# POWER.net
KiCad netlist of a schematic drawn in Altium Designer
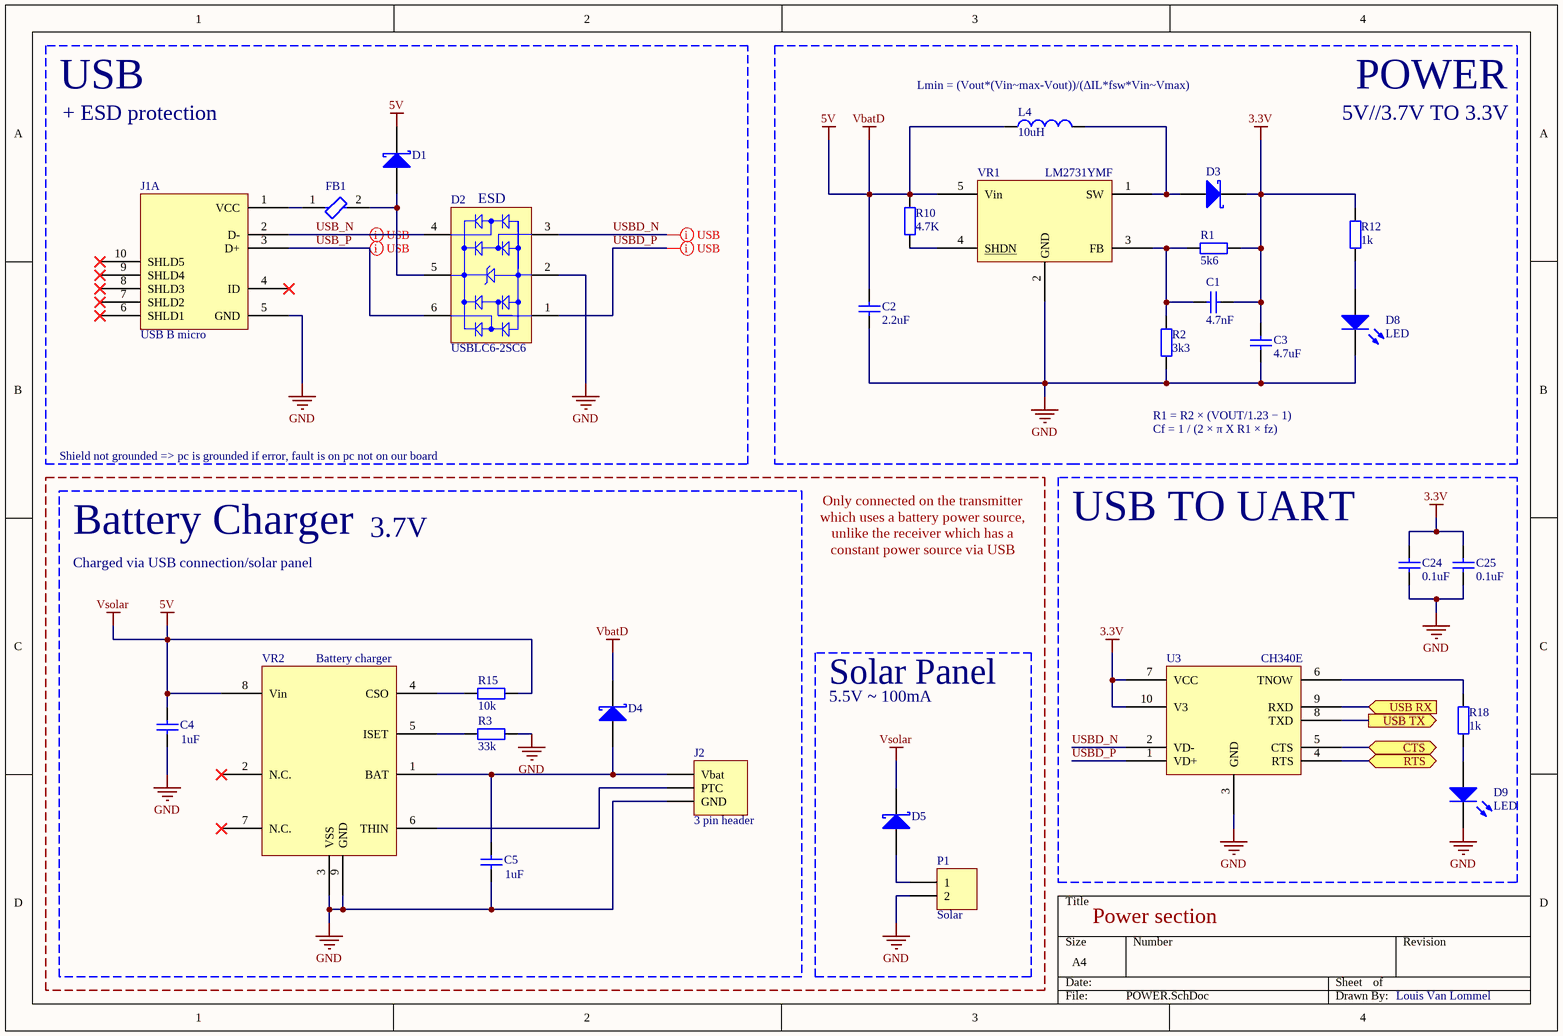
[diagram p0: POWER.SchDoc]

(export (version "E")
  (design (tool "Eeschema 10.0.6"))
  (components
    (comp (ref "C1")
      (value "Cf = 1 / (2 × π X R1 × fz)")
      (footprint "CAP_0603")
      (description "Capacitor")
      (fields (field (name "ALTIUM_VALUE") "4.7nF") (field (name "PUBLISHER") "Altium Limited"))
      (libsource (lib "Miscellaneous Devices") (part "Cap"))
    )
    (comp (ref "C2")
      (value "2.2uF")
      (footprint "CAP_1210")
      (description "Capacitor")
      (fields (field (name "PUBLISHER") "Altium Limited"))
      (libsource (lib "Miscellaneous Devices") (part "Cap"))
    )
    (comp (ref "C3")
      (value "4.7uF")
      (footprint "CAP_1210")
      (description "Capacitor")
      (fields (field (name "PUBLISHER") "Altium Limited"))
      (libsource (lib "Miscellaneous Devices") (part "Cap"))
    )
    (comp (ref "C4")
      (value "1uF")
      (footprint "CAP_0603")
      (description "Capacitor")
      (fields (field (name "PUBLISHER") "Altium Limited"))
      (libsource (lib "Miscellaneous Devices") (part "Cap"))
    )
    (comp (ref "C5")
      (value "1uF")
      (footprint "CAP_0603")
      (description "Capacitor")
      (fields (field (name "PUBLISHER") "Altium Limited"))
      (libsource (lib "Miscellaneous Devices") (part "Cap"))
    )
    (comp (ref "C24")
      (value "0.1uF")
      (footprint "CAP_0603")
      (description "Capacitor")
      (fields (field (name "PUBLISHER") "Altium Limited"))
      (libsource (lib "Miscellaneous Devices") (part "Cap"))
    )
    (comp (ref "C25")
      (value "0.1uF")
      (footprint "CAP_0603")
      (description "Capacitor")
      (fields (field (name "PUBLISHER") "Altium Limited"))
      (libsource (lib "Miscellaneous Devices") (part "Cap"))
    )
    (comp (ref "D1")
      (value "~")
      (footprint "SOT-23_L")
      (description "Silicon RF Schottky Diode for Mixer Applications in the VHF/UHF Range")
      (fields (field (name "PUBLISHER") "Altium Limited"))
      (libsource (lib "Miscellaneous Devices") (part "Diode BAT17"))
    )
    (comp (ref "D2")
      (value "USBLC6-2SC6")
      (footprint "STM-SOT23-6L_V")
      (description "Very low capacitance ESD protection, 3.5 pF, -40 to 125 degC, 6-Pin SOT23, RoHS, Tape and Reel")
      (fields (field (name "MANUFACTURER") "STMicroelectronics"))
      (libsource (lib "Altium Content Vault") (part "STM-USB_DVI_HDMIULC6-4SC6X-SOT23-6L"))
    )
    (comp (ref "D3")
      (value "~")
      (footprint "SOT-23_L")
      (description "Silicon RF Schottky Diode for Mixer Applications in the VHF/UHF Range")
      (fields (field (name "PUBLISHER") "Altium Limited"))
      (libsource (lib "Miscellaneous Devices") (part "Diode BAT17"))
    )
    (comp (ref "D4")
      (value "~")
      (footprint "SOT-23_L")
      (description "Silicon RF Schottky Diode for Mixer Applications in the VHF/UHF Range")
      (fields (field (name "PUBLISHER") "Altium Limited"))
      (libsource (lib "Miscellaneous Devices") (part "Diode BAT17"))
    )
    (comp (ref "D5")
      (value "~")
      (footprint "SOT-23_L")
      (description "Silicon RF Schottky Diode for Mixer Applications in the VHF/UHF Range")
      (fields (field (name "PUBLISHER") "Altium Limited"))
      (libsource (lib "Miscellaneous Devices") (part "Diode BAT17"))
    )
    (comp (ref "D8")
      (value "LED")
      (footprint "LED_0603")
      (description "Typical RED, GREEN, YELLOW, AMBER GaAs LED")
      (fields (field (name "PUBLISHER") "Altium Limited"))
      (libsource (lib "Miscellaneous Devices") (part "LED2"))
    )
    (comp (ref "D9")
      (value "LED")
      (footprint "LED_0603")
      (description "Typical RED, GREEN, YELLOW, AMBER GaAs LED")
      (fields (field (name "PUBLISHER") "Altium Limited"))
      (libsource (lib "Miscellaneous Devices") (part "LED2"))
    )
    (comp (ref "FB1")
      (value "BLM18PG121SN1D")
      (footprint "FP-BLM18-0_15-t0_8-IPC_A")
      (description "Chip Ferrite Bead, 0603, 120Ω @ 100MHz, 0.05Ω, 25%, 2A")
      (fields (field (name "TOLERANCE") "25%"))
      (libsource (lib "Altium Content Vault") (part "5f30dd21d616792df468990f7003faa"))
    )
    (comp (ref "J1")
      (value "USB B micro")
      (footprint "USB Micro B")
      (libsource (lib "AP2112") (part "USB micro B"))
    )
    (comp (ref "J2")
      (value "3 pin header")
      (footprint "Header_3")
      (libsource (lib "AP2112") (part "Header_3"))
    )
    (comp (ref "L4")
      (value "10uH")
      (footprint "INDP7373X45N")
      (description "Inductor")
      (fields (field (name "PUBLISHER") "Altium Limited"))
      (libsource (lib "Miscellaneous Devices") (part "Inductor"))
    )
    (comp (ref "P1")
      (value "Solar")
      (footprint "HDR1X2")
      (description "Header, 2-Pin, Right Angle")
      (fields (field (name "PUBLISHER") "Altium Limited"))
      (libsource (lib "Miscellaneous Connectors") (part "Header 2H"))
    )
    (comp (ref "R1")
      (value "R1 = R2 × (VOUT/1.23 − 1)")
      (footprint "RES_0603")
      (description "Resistor")
      (fields (field (name "ALTIUM_VALUE") "5k6") (field (name "PUBLISHER") "Altium Limited"))
      (libsource (lib "") (part "Res2_2"))
    )
    (comp (ref "R2")
      (value "3k3")
      (footprint "RES_0603")
      (description "Resistor")
      (fields (field (name "PUBLISHER") "Altium Limited"))
      (libsource (lib "Miscellaneous Devices") (part "Res2"))
    )
    (comp (ref "R3")
      (value "33k")
      (footprint "RES_0603")
      (fields (field (name "PUBLISHER") "Altium Limited"))
      (libsource (lib "") (part "Res2_2"))
    )
    (comp (ref "R10")
      (value "4.7K")
      (footprint "RES_0603")
      (description "Resistor")
      (fields (field (name "PUBLISHER") "Altium Limited"))
      (libsource (lib "Miscellaneous Devices") (part "Res2"))
    )
    (comp (ref "R12")
      (value "1k")
      (footprint "RES_0603")
      (description "Resistor")
      (fields (field (name "PUBLISHER") "Altium Limited"))
      (libsource (lib "") (part "Res2_1"))
    )
    (comp (ref "R15")
      (value "10k")
      (footprint "RES_0603")
      (description "Resistor")
      (fields (field (name "PUBLISHER") "Altium Limited"))
      (libsource (lib "") (part "Res2_2"))
    )
    (comp (ref "R18")
      (value "1k")
      (footprint "RES_0603")
      (description "Resistor")
      (fields (field (name "PUBLISHER") "Altium Limited"))
      (libsource (lib "") (part "Res2_1"))
    )
    (comp (ref "U3")
      (value "CH340E")
      (footprint "MSOP-10")
      (description "USB to Serial Uart")
      (libsource (lib "PE2_Schematics") (part "CH340E"))
    )
    (comp (ref "VR1")
      (value "LM2731YMF")
      (footprint "SOT23-5")
      (description "DC-DC Switching Boost (Step Up) Regulator, Adjustable, 2.7V-14Vin, 1.23V-22Vout, 2Aout, SOT-23-5")
      (libsource (lib "PE2_Schematics") (part "LM2731"))
    )
    (comp (ref "VR2")
      (value "Battery charger")
      (footprint "SOP127P600-8N")
      (libsource (lib "PE2_Schematics") (part "XC6804A3E1QR-G"))
    )
  )
  (nets
    (net (code "1") (name "/CTS") (class "Default")
      (node (ref "U3") (pin "5") (pinfunction "CTS_5") (pintype "passive"))
    )
    (net (code "2") (name "/RTS") (class "Default")
      (node (ref "U3") (pin "4") (pinfunction "RTS_4") (pintype "passive"))
    )
    (net (code "3") (name "/USB RX") (class "Default")
      (node (ref "U3") (pin "9") (pinfunction "RXD_9") (pintype "passive"))
    )
    (net (code "4") (name "/USB TX") (class "Default")
      (node (ref "U3") (pin "8") (pinfunction "TXD_8") (pintype "passive"))
    )
    (net (code "5") (name "/USBD_N") (class "Default")
      (node (ref "D2") (pin "3") (pinfunction "I/O_2_3") (pintype "passive"))
      (node (ref "U3") (pin "2") (pinfunction "VD-_2") (pintype "passive"))
    )
    (net (code "6") (name "/USBD_P") (class "Default")
      (node (ref "D2") (pin "1") (pinfunction "I/O_1_1") (pintype "passive"))
      (node (ref "U3") (pin "1") (pinfunction "VD+_1") (pintype "passive"))
    )
    (net (code "7") (name "/USB_N") (class "Default")
      (node (ref "D2") (pin "4") (pinfunction "I/O_3_4") (pintype "passive"))
      (node (ref "J1") (pin "2") (pinfunction "D-_2") (pintype "passive"))
    )
    (net (code "8") (name "/USB_P") (class "Default")
      (node (ref "D2") (pin "6") (pinfunction "I/O_4_6") (pintype "passive"))
      (node (ref "J1") (pin "3") (pinfunction "D+_3") (pintype "passive"))
    )
    (net (code "9") (name "3.3V") (class "Default")
      (node (ref "C1") (pin "1") (pinfunction "1_1") (pintype "passive"))
      (node (ref "C24") (pin "1") (pinfunction "1_1") (pintype "passive"))
      (node (ref "C25") (pin "1") (pinfunction "1_1") (pintype "passive"))
      (node (ref "C3") (pin "1") (pinfunction "1_1") (pintype "passive"))
      (node (ref "D3") (pin "3") (pinfunction "K_3") (pintype "passive"))
      (node (ref "R1") (pin "1") (pinfunction "1_1") (pintype "passive"))
      (node (ref "R12") (pin "2") (pinfunction "2_2") (pintype "passive"))
      (node (ref "U3") (pin "10") (pinfunction "V3_10") (pintype "passive"))
      (node (ref "U3") (pin "7") (pinfunction "VCC_7") (pintype "passive"))
    )
    (net (code "10") (name "5V") (class "Default")
      (node (ref "C2") (pin "1") (pinfunction "1_1") (pintype "passive"))
      (node (ref "C4") (pin "2") (pinfunction "2_2") (pintype "passive"))
      (node (ref "D1") (pin "3") (pinfunction "K_3") (pintype "passive"))
      (node (ref "D4") (pin "3") (pinfunction "K_3") (pintype "passive"))
      (node (ref "D5") (pin "3") (pinfunction "K_3") (pintype "passive"))
      (node (ref "L4") (pin "1") (pinfunction "1_1") (pintype "passive"))
      (node (ref "R10") (pin "1") (pinfunction "1_1") (pintype "passive"))
      (node (ref "R15") (pin "1") (pinfunction "1_1") (pintype "passive"))
      (node (ref "VR1") (pin "5") (pinfunction "Vin_5") (pintype "passive"))
      (node (ref "VR2") (pin "8") (pinfunction "Vin_8") (pintype "passive"))
    )
    (net (code "11") (name "GND") (class "Default")
      (node (ref "C2") (pin "2") (pinfunction "2_2") (pintype "passive"))
      (node (ref "C24") (pin "2") (pinfunction "2_2") (pintype "passive"))
      (node (ref "C25") (pin "2") (pinfunction "2_2") (pintype "passive"))
      (node (ref "C3") (pin "2") (pinfunction "2_2") (pintype "passive"))
      (node (ref "C4") (pin "1") (pinfunction "1_1") (pintype "passive"))
      (node (ref "C5") (pin "1") (pinfunction "1_1") (pintype "passive"))
      (node (ref "D2") (pin "2") (pinfunction "GND_2") (pintype "passive"))
      (node (ref "D8") (pin "2") (pinfunction "K_2") (pintype "passive"))
      (node (ref "D9") (pin "2") (pinfunction "K_2") (pintype "passive"))
      (node (ref "J1") (pin "5") (pinfunction "GND_5") (pintype "passive"))
      (node (ref "J2") (pin "3") (pinfunction "GND_3") (pintype "passive"))
      (node (ref "P1") (pin "2") (pinfunction "2_2") (pintype "passive"))
      (node (ref "R2") (pin "2") (pinfunction "2_2") (pintype "passive"))
      (node (ref "R3") (pin "1") (pinfunction "1_1") (pintype "passive"))
      (node (ref "U3") (pin "3") (pinfunction "GND_3") (pintype "passive"))
      (node (ref "VR1") (pin "2") (pinfunction "GND_2") (pintype "passive"))
      (node (ref "VR2") (pin "3") (pinfunction "VSS_3") (pintype "passive"))
      (node (ref "VR2") (pin "9") (pinfunction "GND_9") (pintype "passive"))
    )
    (net (code "12") (name "Net-(D1-A)") (class "Default")
      (node (ref "D1") (pin "1") (pinfunction "A_1") (pintype "passive"))
      (node (ref "D2") (pin "5") (pinfunction "VBUS_5") (pintype "passive"))
      (node (ref "FB1") (pin "2") (pinfunction "2_2") (pintype "passive"))
    )
    (net (code "13") (name "Net-(D3-A)") (class "Default")
      (node (ref "D3") (pin "1") (pinfunction "A_1") (pintype "passive"))
      (node (ref "L4") (pin "2") (pinfunction "2_2") (pintype "passive"))
      (node (ref "VR1") (pin "1") (pinfunction "SW_1") (pintype "passive"))
    )
    (net (code "14") (name "Net-(D4-A)") (class "Default")
      (node (ref "C5") (pin "2") (pinfunction "2_2") (pintype "passive"))
      (node (ref "D4") (pin "1") (pinfunction "A_1") (pintype "passive"))
      (node (ref "J2") (pin "1") (pinfunction "Vbat_1") (pintype "passive"))
      (node (ref "VR2") (pin "1") (pinfunction "BAT_1") (pintype "passive"))
    )
    (net (code "15") (name "Net-(D5-A)") (class "Default")
      (node (ref "D5") (pin "1") (pinfunction "A_1") (pintype "passive"))
      (node (ref "P1") (pin "1") (pinfunction "1_1") (pintype "passive"))
    )
    (net (code "16") (name "Net-(D8-A)") (class "Default")
      (node (ref "D8") (pin "1") (pinfunction "A_1") (pintype "passive"))
      (node (ref "R12") (pin "1") (pinfunction "1_1") (pintype "passive"))
    )
    (net (code "17") (name "Net-(D9-A)") (class "Default")
      (node (ref "D9") (pin "1") (pinfunction "A_1") (pintype "passive"))
      (node (ref "R18") (pin "1") (pinfunction "1_1") (pintype "passive"))
    )
    (net (code "18") (name "Net-(J1-VCC)") (class "Default")
      (node (ref "FB1") (pin "1") (pinfunction "1_1") (pintype "passive"))
      (node (ref "J1") (pin "1") (pinfunction "VCC_1") (pintype "passive"))
    )
    (net (code "19") (name "Net-(J2-PTC)") (class "Default")
      (node (ref "J2") (pin "2") (pinfunction "PTC_2") (pintype "passive"))
      (node (ref "VR2") (pin "6") (pinfunction "THIN_6") (pintype "passive"))
    )
    (net (code "20") (name "Net-(U3-TNOW)") (class "Default")
      (node (ref "R18") (pin "2") (pinfunction "2_2") (pintype "passive"))
      (node (ref "U3") (pin "6") (pinfunction "TNOW_6") (pintype "passive"))
    )
    (net (code "21") (name "Net-(VR1-FB)") (class "Default")
      (node (ref "C1") (pin "2") (pinfunction "2_2") (pintype "passive"))
      (node (ref "R1") (pin "2") (pinfunction "2_2") (pintype "passive"))
      (node (ref "R2") (pin "1") (pinfunction "1_1") (pintype "passive"))
      (node (ref "VR1") (pin "3") (pinfunction "FB_3") (pintype "passive"))
    )
    (net (code "22") (name "Net-(VR1-SHDN)") (class "Default")
      (node (ref "R10") (pin "2") (pinfunction "2_2") (pintype "passive"))
      (node (ref "VR1") (pin "4") (pinfunction "SHDN_4") (pintype "passive"))
    )
    (net (code "23") (name "Net-(VR2-CSO)") (class "Default")
      (node (ref "R15") (pin "2") (pinfunction "2_2") (pintype "passive"))
      (node (ref "VR2") (pin "4") (pinfunction "CSO_4") (pintype "passive"))
    )
    (net (code "24") (name "Net-(VR2-ISET)") (class "Default")
      (node (ref "R3") (pin "2") (pinfunction "2_2") (pintype "passive"))
      (node (ref "VR2") (pin "5") (pinfunction "ISET_5") (pintype "passive"))
    )
    (net (code "25") (name "unconnected-(J1-ID-Pad4)") (class "Default")
      (node (ref "J1") (pin "4") (pinfunction "ID_4") (pintype "passive+no_connect"))
    )
    (net (code "26") (name "unconnected-(J1-SHLD1-Pad6)") (class "Default")
      (node (ref "J1") (pin "6") (pinfunction "SHLD1_6") (pintype "passive+no_connect"))
    )
    (net (code "27") (name "unconnected-(J1-SHLD2-Pad7)") (class "Default")
      (node (ref "J1") (pin "7") (pinfunction "SHLD2_7") (pintype "passive+no_connect"))
    )
    (net (code "28") (name "unconnected-(J1-SHLD3-Pad8)") (class "Default")
      (node (ref "J1") (pin "8") (pinfunction "SHLD3_8") (pintype "passive+no_connect"))
    )
    (net (code "29") (name "unconnected-(J1-SHLD4-Pad9)") (class "Default")
      (node (ref "J1") (pin "9") (pinfunction "SHLD4_9") (pintype "passive+no_connect"))
    )
    (net (code "30") (name "unconnected-(J1-SHLD5-Pad10)") (class "Default")
      (node (ref "J1") (pin "10") (pinfunction "SHLD5_10") (pintype "passive+no_connect"))
    )
    (net (code "31") (name "unconnected-(VR2-N.C.-Pad2)") (class "Default")
      (node (ref "VR2") (pin "2") (pinfunction "N.C._2") (pintype "passive+no_connect"))
    )
    (net (code "32") (name "unconnected-(VR2-N.C.-Pad7)") (class "Default")
      (node (ref "VR2") (pin "7") (pinfunction "N.C._7") (pintype "passive+no_connect"))
    )
  )
)
